# rapidshark-butt-break-mk-1_0.net
KiCad netlist of a schematic drawn in EAGLE
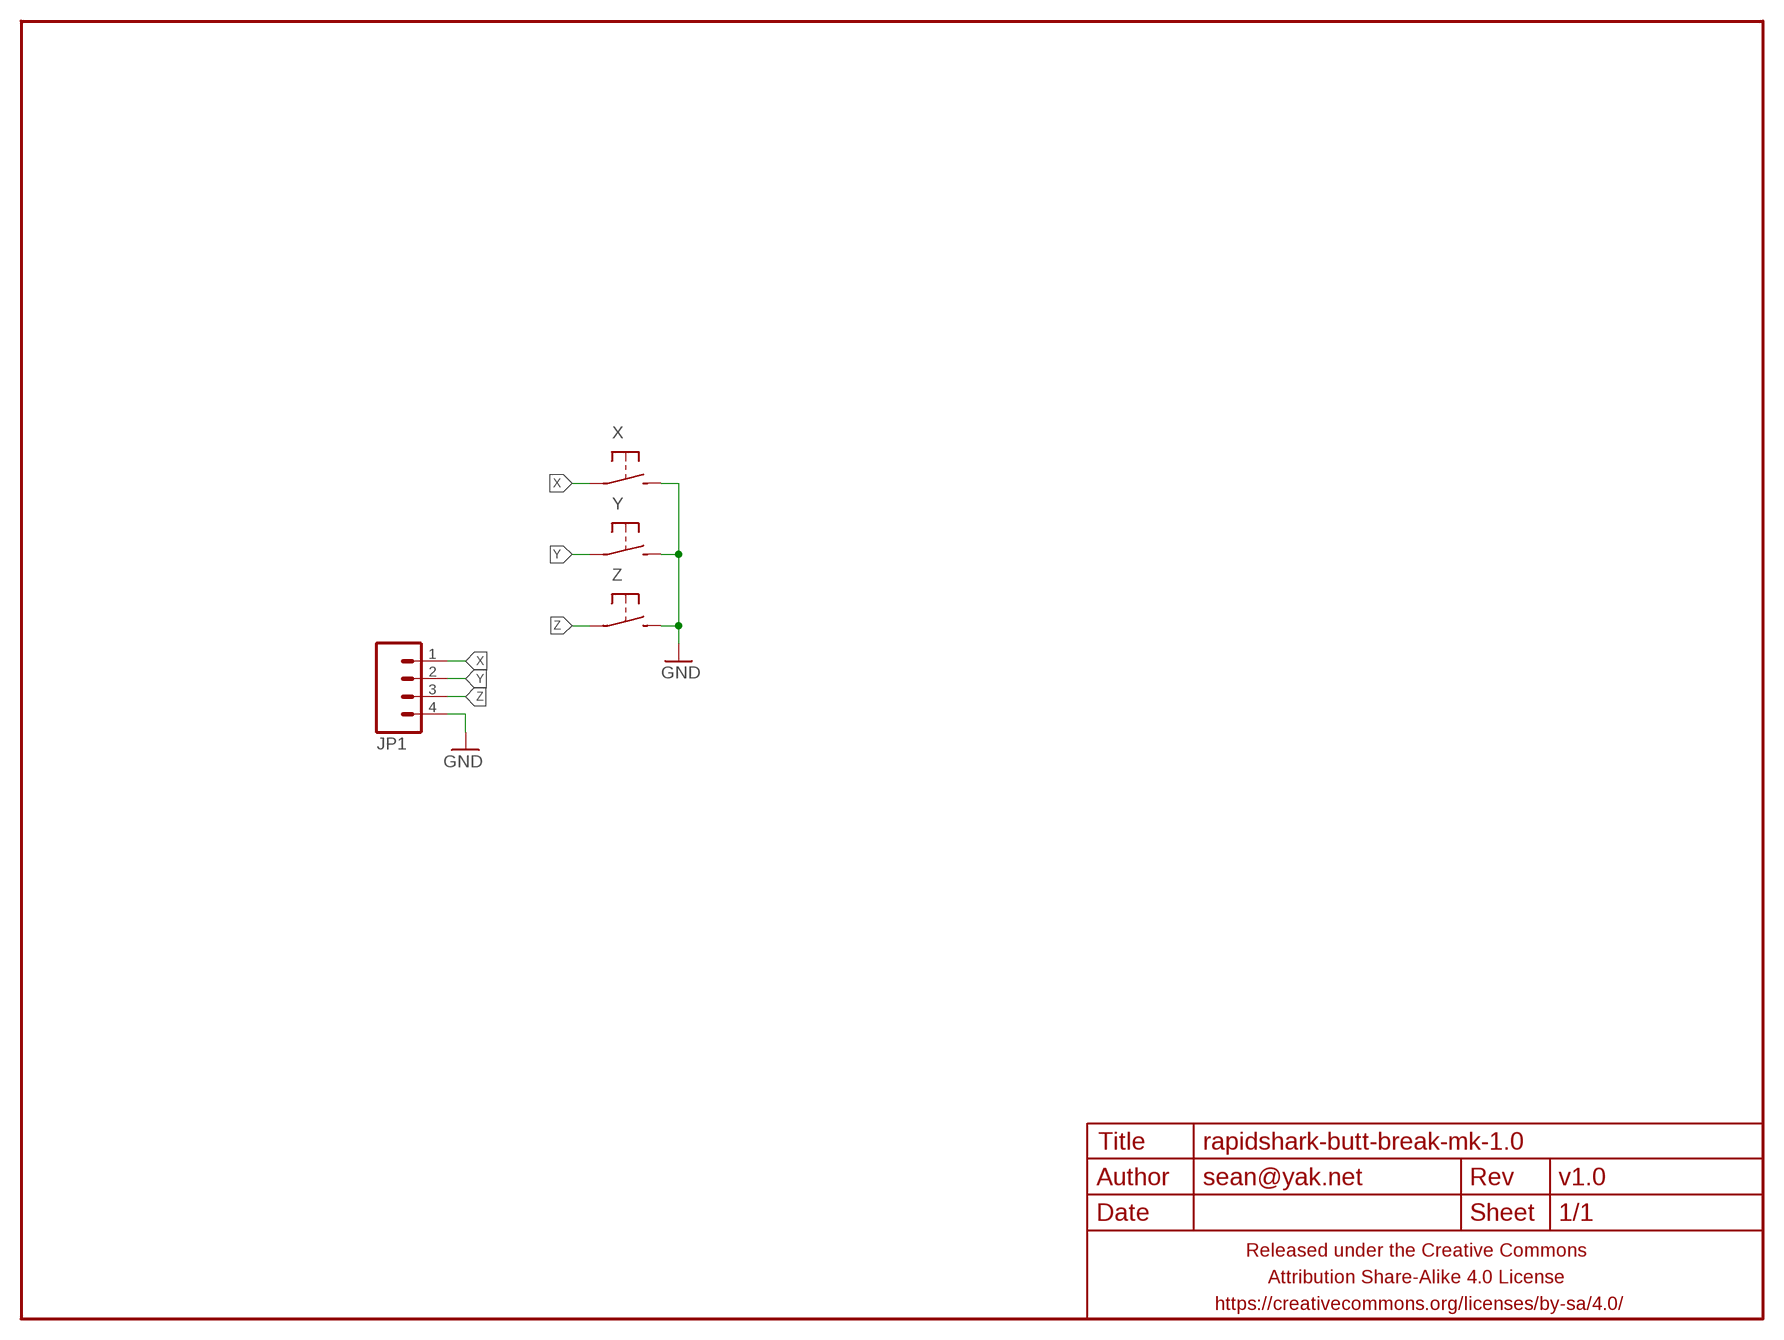
[diagram p0: schematic, sheet 1]

(export (version "E")
  (design (tool "Eeschema 10.0.6"))
  (components
    (comp (ref "FRAME1")
      (value "FRAME-LETTERNO_PACKAGE")
      (footprint "eagle-import:DUMMY")
      (fields (field (name "DESIGNER") "sean@yak.net") (field (name "VERSION") "v1.0"))
      (libsource (lib "eagle-import") (part "FRAME-LETTERNO_PACKAGE"))
    )
    (comp (ref "JP1")
      (value "M04JST-PTH")
      (footprint "eagle-import:JST-4-PH-RA-PTH")
      (libsource (lib "eagle-import") (part "M04JST-PTH"))
    )
    (comp (ref "X")
      (value "SPST-NO-TACT3MM-PTH-SMALL-PADS")
      (footprint "eagle-import:DTS-3-SMALL-PADS")
      (libsource (lib "eagle-import") (part "SPST-NO-TACT3MM-PTH-SMALL-PADS"))
    )
    (comp (ref "Y")
      (value "SPST-NO-TACT3MM-PTH-SMALL-PADS")
      (footprint "eagle-import:DTS-3-SMALL-PADS")
      (libsource (lib "eagle-import") (part "SPST-NO-TACT3MM-PTH-SMALL-PADS"))
    )
    (comp (ref "Z")
      (value "SPST-NO-TACT3MM-PTH-SMALL-PADS")
      (footprint "eagle-import:DTS-3-SMALL-PADS")
      (libsource (lib "eagle-import") (part "SPST-NO-TACT3MM-PTH-SMALL-PADS"))
    )
  )
  (nets
    (net (code "1") (name "GND") (class "Default")
      (node (ref "JP1") (pin "4") (pinfunction "4_4") (pintype "passive"))
      (node (ref "X") (pin "2") (pinfunction "2_2") (pintype "passive"))
      (node (ref "Y") (pin "2") (pinfunction "2_2") (pintype "passive"))
      (node (ref "Z") (pin "2") (pinfunction "2_2") (pintype "passive"))
    )
    (net (code "2") (name "X") (class "Default")
      (node (ref "JP1") (pin "1") (pinfunction "1_1") (pintype "passive"))
      (node (ref "X") (pin "1") (pinfunction "1_1") (pintype "passive"))
    )
    (net (code "3") (name "Y") (class "Default")
      (node (ref "JP1") (pin "2") (pinfunction "2_2") (pintype "passive"))
      (node (ref "Y") (pin "1") (pinfunction "1_1") (pintype "passive"))
    )
    (net (code "4") (name "Z") (class "Default")
      (node (ref "JP1") (pin "3") (pinfunction "3_3") (pintype "passive"))
      (node (ref "Z") (pin "1") (pinfunction "1_1") (pintype "passive"))
    )
  )
)
